# momav_esc.net
KiCad netlist of a schematic drawn in EAGLE
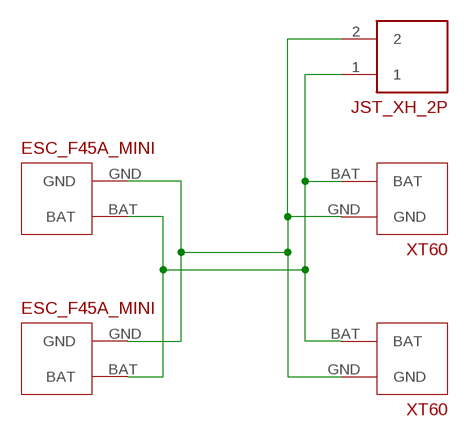
[diagram p0: schematic, sheet 1]

(export (version "E")
  (design (tool "Eeschema 10.0.6"))
  (components
    (comp (ref "U$1")
      (value "ESC_F45A_MINI")
      (footprint "eagle-import:ESC_F45A_MINI")
      (libsource (lib "eagle-import") (part "ESC_F45A_MINI"))
    )
    (comp (ref "U$2")
      (value "ESC_F45A_MINI")
      (footprint "eagle-import:ESC_F45A_MINI")
      (libsource (lib "eagle-import") (part "ESC_F45A_MINI"))
    )
    (comp (ref "U$3")
      (value "CONN_XT60")
      (footprint "eagle-import:CONN_XT60")
      (libsource (lib "eagle-import") (part "CONN_XT60"))
    )
    (comp (ref "U$4")
      (value "CONN_XT60")
      (footprint "eagle-import:CONN_XT60")
      (libsource (lib "eagle-import") (part "CONN_XT60"))
    )
    (comp (ref "U$5")
      (value "JST_XH_2P")
      (footprint "eagle-import:JST_XH_2P")
      (libsource (lib "eagle-import") (part "JST_XH_2P"))
    )
  )
  (nets
    (net (code "1") (name "Net-(U$1-PadBAT)") (class "Default")
      (node (ref "U$1") (pin "BAT") (pinfunction "BAT_BAT") (pintype "bidirectional"))
      (node (ref "U$2") (pin "BAT") (pinfunction "BAT_BAT") (pintype "bidirectional"))
      (node (ref "U$3") (pin "BAT") (pinfunction "BAT_BAT") (pintype "bidirectional"))
      (node (ref "U$4") (pin "BAT") (pinfunction "BAT_BAT") (pintype "bidirectional"))
      (node (ref "U$5") (pin "1") (pinfunction "1_1") (pintype "bidirectional"))
    )
    (net (code "2") (name "Net-(U$1-PadGND)") (class "Default")
      (node (ref "U$1") (pin "GND") (pinfunction "GND_GND") (pintype "bidirectional"))
      (node (ref "U$2") (pin "GND") (pinfunction "GND_GND") (pintype "bidirectional"))
      (node (ref "U$3") (pin "GND") (pinfunction "GND_GND") (pintype "bidirectional"))
      (node (ref "U$4") (pin "GND") (pinfunction "GND_GND") (pintype "bidirectional"))
      (node (ref "U$5") (pin "2") (pinfunction "2_2") (pintype "bidirectional"))
    )
  )
)
